# 03-PeripheralPart-V2_4.net
KiCad netlist of a schematic drawn in Altium Designer
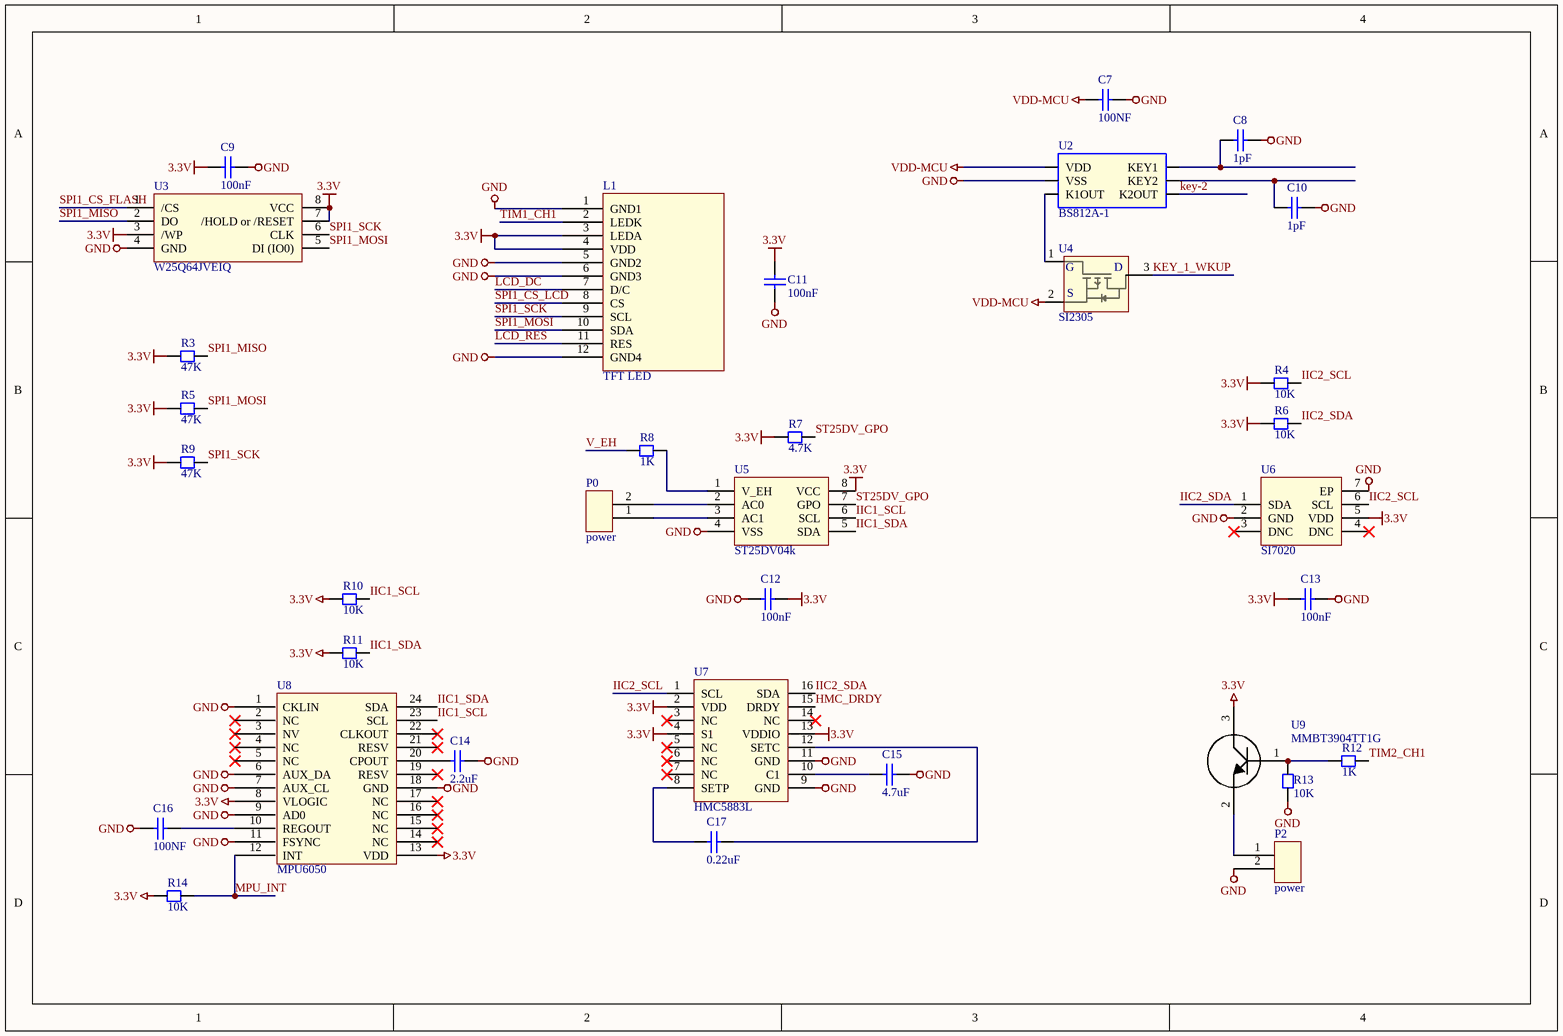
[diagram p0: 03-PeripheralPart-V2.4.SchDoc]

(export (version "E")
  (design (tool "Eeschema 10.0.6"))
  (components
    (comp (ref "C7")
      (value "100NF")
      (footprint "CC1005-0402")
      (description "贴片电容")
      (libsource (lib "tianxiaohua_Schlib") (part "Chip capacitor"))
    )
    (comp (ref "C8")
      (value "1pF")
      (footprint "CC1005-0402")
      (description "贴片电容")
      (libsource (lib "tianxiaohua_Schlib") (part "Chip capacitor"))
    )
    (comp (ref "C9")
      (value "100nF")
      (footprint "CC1005-0402")
      (description "贴片电容")
      (libsource (lib "tianxiaohua_Schlib") (part "Chip capacitor"))
    )
    (comp (ref "C10")
      (value "1pF")
      (footprint "CC1005-0402")
      (description "贴片电容")
      (libsource (lib "tianxiaohua_Schlib") (part "Chip capacitor"))
    )
    (comp (ref "C11")
      (value "100nF")
      (footprint "CC1005-0402")
      (description "贴片电容")
      (libsource (lib "tianxiaohua_Schlib") (part "Chip capacitor"))
    )
    (comp (ref "C12")
      (value "100nF")
      (footprint "CC1005-0402")
      (description "贴片电容")
      (libsource (lib "tianxiaohua_Schlib") (part "Chip capacitor"))
    )
    (comp (ref "C13")
      (value "100nF")
      (footprint "CC1005-0402")
      (description "贴片电容")
      (libsource (lib "tianxiaohua_Schlib") (part "Chip capacitor"))
    )
    (comp (ref "C14")
      (value "2.2uF")
      (footprint "CC1005-0402")
      (description "贴片电容")
      (libsource (lib "tianxiaohua_Schlib") (part "Chip capacitor"))
    )
    (comp (ref "C15")
      (value "4.7uF")
      (footprint "CC1005-0402")
      (description "贴片电容")
      (libsource (lib "tianxiaohua_Schlib") (part "Chip capacitor"))
    )
    (comp (ref "C16")
      (value "100NF")
      (footprint "CC1005-0402")
      (description "贴片电容")
      (libsource (lib "tianxiaohua_Schlib") (part "Chip capacitor"))
    )
    (comp (ref "C17")
      (value "0.22uF")
      (footprint "CC1005-0402")
      (description "贴片电容")
      (libsource (lib "tianxiaohua_Schlib") (part "Chip capacitor"))
    )
    (comp (ref "L1")
      (value "TFT LED")
      (footprint "LCD-1.3-(2)")
      (description "1.3寸显示屏幕")
      (libsource (lib "tianxiaohua_Schlib") (part "LCD-IPSscreen-1.3"))
    )
    (comp (ref "P0") (value "power") (footprint "POWER2") (libsource (lib "") (part "power_1")))
    (comp (ref "P2")
      (value "power")
      (footprint "POWER-3.7V")
      (libsource (lib "tianxiaohua_Schlib") (part "power"))
    )
    (comp (ref "R3")
      (value "47K")
      (footprint "CR1005-0402")
      (description "贴片电阻")
      (libsource (lib "") (part "Chip resistor_1"))
    )
    (comp (ref "R4")
      (value "10K")
      (footprint "CR1005-0402")
      (description "贴片电阻")
      (libsource (lib "") (part "Chip resistor_1"))
    )
    (comp (ref "R5")
      (value "47K")
      (footprint "CR1005-0402")
      (description "贴片电阻")
      (libsource (lib "") (part "Chip resistor_1"))
    )
    (comp (ref "R6")
      (value "10K")
      (footprint "CR1005-0402")
      (description "贴片电阻")
      (libsource (lib "") (part "Chip resistor_1"))
    )
    (comp (ref "R7")
      (value "4.7K")
      (footprint "CR1005-0402")
      (description "贴片电阻")
      (libsource (lib "") (part "Chip resistor_2"))
    )
    (comp (ref "R8")
      (value "1K")
      (footprint "CR1005-0402")
      (description "贴片电阻")
      (libsource (lib "") (part "Chip resistor_1"))
    )
    (comp (ref "R9")
      (value "47K")
      (footprint "CR1005-0402")
      (description "贴片电阻")
      (libsource (lib "") (part "Chip resistor_1"))
    )
    (comp (ref "R10")
      (value "10K")
      (footprint "CR1005-0402")
      (description "贴片电阻")
      (libsource (lib "") (part "Chip resistor_1"))
    )
    (comp (ref "R11")
      (value "10K")
      (footprint "CR1005-0402")
      (description "贴片电阻")
      (libsource (lib "") (part "Chip resistor_1"))
    )
    (comp (ref "R12")
      (value "1K")
      (footprint "CR1005-0402")
      (description "贴片电阻")
      (libsource (lib "") (part "Chip resistor_1"))
    )
    (comp (ref "R13")
      (value "10K")
      (footprint "CR1005-0402")
      (description "贴片电阻")
      (libsource (lib "tianxiaohua_Schlib") (part "Chip resistor"))
    )
    (comp (ref "R14")
      (value "10K")
      (footprint "CR1005-0402")
      (description "贴片电阻")
      (libsource (lib "") (part "Chip resistor_1"))
    )
    (comp (ref "U2")
      (value "BS812A-1")
      (footprint "SOT23-6")
      (description "触摸按键 两路 SOP23-6封装极简电路")
      (libsource (lib "tianxiaohua_Schlib") (part "BS812A-1"))
    )
    (comp (ref "U3")
      (value "W25Q64JVEIQ")
      (footprint "WSON-8_L8.0-W6.10-P1.27-TL-EP")
      (description "FLASH")
      (libsource (lib "tianxiaohua_Schlib") (part "W25Q256JVEIQ"))
    )
    (comp (ref "U4")
      (value "SI2305")
      (footprint "SOT-23")
      (description "PMOS场效应MOS管 SOT-23")
      (libsource (lib "tianxiaohua_Schlib") (part "SI2305"))
    )
    (comp (ref "U5")
      (value "ST25DV04k")
      (footprint "UFDFPN8")
      (description "NFC芯片4K存储空间")
      (libsource (lib "tianxiaohua_Schlib") (part "ST25DV04k"))
    )
    (comp (ref "U6")
      (value "SI7020")
      (footprint "DFN-6")
      (description "温湿度传感器芯片")
      (libsource (lib "tianxiaohua_Schlib") (part "SI7020"))
    )
    (comp (ref "U7")
      (value "HMC5883L")
      (footprint "LPCC-16_L3.0-W3.0-P0.50-BL")
      (description "三轴罗盘")
      (libsource (lib "tianxiaohua_Schlib") (part "HMC5883L"))
    )
    (comp (ref "U8")
      (value "MPU6050")
      (footprint "QFN24 - duplicate")
      (description "陀螺仪")
      (libsource (lib "tianxiaohua_Schlib") (part "MPU6050"))
    )
    (comp (ref "U9")
      (value "MMBT3904TT1G")
      (footprint "SOT-416")
      (description "NPN 电流 - 集电极（Ic）（最大值）：200mA 电压 - 集射极击穿（最大值）：40V SOT-23-3")
      (libsource (lib "tianxiaohua_Schlib") (part "MMBT3904TT1G"))
    )
  )
  (nets
    (net (code "1") (name "/HMC_DRDY") (class "Default")
      (node (ref "U7") (pin "15") (pinfunction "DRDY_15") (pintype "passive"))
    )
    (net (code "2") (name "/IIC1_SCL") (class "Default")
      (node (ref "R10") (pin "1") (pinfunction "1_1") (pintype "passive"))
      (node (ref "U5") (pin "6") (pinfunction "SCL_6") (pintype "passive"))
      (node (ref "U8") (pin "23") (pinfunction "SCL_23") (pintype "passive"))
    )
    (net (code "3") (name "/IIC1_SDA") (class "Default")
      (node (ref "R11") (pin "1") (pinfunction "1_1") (pintype "passive"))
      (node (ref "U5") (pin "5") (pinfunction "SDA_5") (pintype "passive"))
      (node (ref "U8") (pin "24") (pinfunction "SDA_24") (pintype "passive"))
    )
    (net (code "4") (name "/IIC2_SCL") (class "Default")
      (node (ref "R4") (pin "1") (pinfunction "1_1") (pintype "passive"))
      (node (ref "U6") (pin "6") (pinfunction "SCL_6") (pintype "passive"))
      (node (ref "U7") (pin "1") (pinfunction "SCL_1") (pintype "passive"))
    )
    (net (code "5") (name "/IIC2_SDA") (class "Default")
      (node (ref "R6") (pin "1") (pinfunction "1_1") (pintype "passive"))
      (node (ref "U6") (pin "1") (pinfunction "SDA_1") (pintype "passive"))
      (node (ref "U7") (pin "16") (pinfunction "SDA_16") (pintype "passive"))
    )
    (net (code "6") (name "/KEY_1_WKUP") (class "Default")
      (node (ref "U4") (pin "3") (pinfunction "DRAIN_3") (pintype "passive"))
    )
    (net (code "7") (name "/LCD_DC") (class "Default")
      (node (ref "L1") (pin "7") (pinfunction "D/C_7") (pintype "passive"))
    )
    (net (code "8") (name "/LCD_RES") (class "Default")
      (node (ref "L1") (pin "11") (pinfunction "RES_11") (pintype "passive"))
    )
    (net (code "9") (name "/MPU_INT") (class "Default")
      (node (ref "R14") (pin "1") (pinfunction "1_1") (pintype "passive"))
      (node (ref "U8") (pin "12") (pinfunction "INT_12") (pintype "passive"))
    )
    (net (code "10") (name "/SPI1_CS_FLASH") (class "Default")
      (node (ref "U3") (pin "1") (pinfunction "/CS_1") (pintype "passive"))
    )
    (net (code "11") (name "/SPI1_CS_LCD") (class "Default")
      (node (ref "L1") (pin "8") (pinfunction "CS_8") (pintype "passive"))
    )
    (net (code "12") (name "/SPI1_MISO") (class "Default")
      (node (ref "R3") (pin "1") (pinfunction "1_1") (pintype "passive"))
      (node (ref "U3") (pin "2") (pinfunction "DO_2") (pintype "passive"))
    )
    (net (code "13") (name "/SPI1_MOSI") (class "Default")
      (node (ref "L1") (pin "10") (pinfunction "SDA_10") (pintype "passive"))
      (node (ref "R5") (pin "1") (pinfunction "1_1") (pintype "passive"))
      (node (ref "U3") (pin "5") (pinfunction "DI_(IO0)_5") (pintype "passive"))
    )
    (net (code "14") (name "/SPI1_SCK") (class "Default")
      (node (ref "L1") (pin "9") (pinfunction "SCL_9") (pintype "passive"))
      (node (ref "R9") (pin "1") (pinfunction "1_1") (pintype "passive"))
      (node (ref "U3") (pin "6") (pinfunction "CLK_6") (pintype "passive"))
    )
    (net (code "15") (name "/ST25DV_GPO") (class "Default")
      (node (ref "R7") (pin "2") (pinfunction "2_2") (pintype "passive"))
      (node (ref "U5") (pin "7") (pinfunction "GPO_7") (pintype "passive"))
    )
    (net (code "16") (name "/TIM1_CH1") (class "Default")
      (node (ref "L1") (pin "2") (pinfunction "LEDK_2") (pintype "passive"))
    )
    (net (code "17") (name "/TIM2_CH1") (class "Default")
      (node (ref "R12") (pin "1") (pinfunction "1_1") (pintype "passive"))
    )
    (net (code "18") (name "/V_EH") (class "Default")
      (node (ref "R8") (pin "2") (pinfunction "2_2") (pintype "passive"))
    )
    (net (code "19") (name "/key-2") (class "Default")
      (node (ref "U2") (pin "4") (pinfunction "K2OUT_4") (pintype "passive"))
    )
    (net (code "20") (name "3.3V") (class "Default")
      (node (ref "C11") (pin "1") (pinfunction "1_1") (pintype "passive"))
      (node (ref "C12") (pin "2") (pinfunction "2_2") (pintype "passive"))
      (node (ref "C13") (pin "1") (pinfunction "1_1") (pintype "passive"))
      (node (ref "C9") (pin "1") (pinfunction "1_1") (pintype "passive"))
      (node (ref "L1") (pin "3") (pinfunction "LEDA_3") (pintype "passive"))
      (node (ref "L1") (pin "4") (pinfunction "VDD_4") (pintype "passive"))
      (node (ref "R10") (pin "2") (pinfunction "2_2") (pintype "passive"))
      (node (ref "R11") (pin "2") (pinfunction "2_2") (pintype "passive"))
      (node (ref "R14") (pin "2") (pinfunction "2_2") (pintype "passive"))
      (node (ref "R3") (pin "2") (pinfunction "2_2") (pintype "passive"))
      (node (ref "R4") (pin "2") (pinfunction "2_2") (pintype "passive"))
      (node (ref "R5") (pin "2") (pinfunction "2_2") (pintype "passive"))
      (node (ref "R6") (pin "2") (pinfunction "2_2") (pintype "passive"))
      (node (ref "R7") (pin "1") (pinfunction "1_1") (pintype "passive"))
      (node (ref "R9") (pin "2") (pinfunction "2_2") (pintype "passive"))
      (node (ref "U3") (pin "3") (pinfunction "/WP_3") (pintype "passive"))
      (node (ref "U3") (pin "7") (pinfunction "/HOLD_or_/RESET_7") (pintype "passive"))
      (node (ref "U3") (pin "8") (pinfunction "VCC_8") (pintype "passive"))
      (node (ref "U5") (pin "8") (pinfunction "VCC_8") (pintype "passive"))
      (node (ref "U6") (pin "5") (pinfunction "VDD_5") (pintype "passive"))
      (node (ref "U7") (pin "13") (pinfunction "VDDIO_13") (pintype "passive"))
      (node (ref "U7") (pin "2") (pinfunction "VDD_2") (pintype "passive"))
      (node (ref "U7") (pin "4") (pinfunction "S1_4") (pintype "passive"))
      (node (ref "U8") (pin "13") (pinfunction "VDD_13") (pintype "passive"))
      (node (ref "U8") (pin "8") (pinfunction "VLOGIC_8") (pintype "passive"))
      (node (ref "U9") (pin "3") (pinfunction "3_3") (pintype "passive"))
    )
    (net (code "21") (name "GND") (class "Default")
      (node (ref "C10") (pin "2") (pinfunction "2_2") (pintype "passive"))
      (node (ref "C11") (pin "2") (pinfunction "2_2") (pintype "passive"))
      (node (ref "C12") (pin "1") (pinfunction "1_1") (pintype "passive"))
      (node (ref "C13") (pin "2") (pinfunction "2_2") (pintype "passive"))
      (node (ref "C14") (pin "2") (pinfunction "2_2") (pintype "passive"))
      (node (ref "C15") (pin "2") (pinfunction "2_2") (pintype "passive"))
      (node (ref "C16") (pin "1") (pinfunction "1_1") (pintype "passive"))
      (node (ref "C7") (pin "1") (pinfunction "1_1") (pintype "passive"))
      (node (ref "C8") (pin "2") (pinfunction "2_2") (pintype "passive"))
      (node (ref "C9") (pin "2") (pinfunction "2_2") (pintype "passive"))
      (node (ref "L1") (pin "1") (pinfunction "GND1_1") (pintype "passive"))
      (node (ref "L1") (pin "12") (pinfunction "GND4_12") (pintype "passive"))
      (node (ref "L1") (pin "5") (pinfunction "GND2_5") (pintype "passive"))
      (node (ref "L1") (pin "6") (pinfunction "GND3_6") (pintype "passive"))
      (node (ref "P2") (pin "2") (pinfunction "2_2") (pintype "passive"))
      (node (ref "R13") (pin "2") (pinfunction "2_2") (pintype "passive"))
      (node (ref "U2") (pin "2") (pinfunction "VSS_2") (pintype "passive"))
      (node (ref "U3") (pin "4") (pinfunction "GND_4") (pintype "passive"))
      (node (ref "U5") (pin "4") (pinfunction "VSS_4") (pintype "passive"))
      (node (ref "U6") (pin "2") (pinfunction "GND_2") (pintype "passive"))
      (node (ref "U6") (pin "7") (pinfunction "EP_7") (pintype "passive"))
      (node (ref "U7") (pin "11") (pinfunction "GND_11") (pintype "passive"))
      (node (ref "U7") (pin "9") (pinfunction "GND_9") (pintype "passive"))
      (node (ref "U8") (pin "1") (pinfunction "CKLIN_1") (pintype "passive"))
      (node (ref "U8") (pin "11") (pinfunction "FSYNC_11") (pintype "passive"))
      (node (ref "U8") (pin "18") (pinfunction "GND_18") (pintype "passive"))
      (node (ref "U8") (pin "6") (pinfunction "AUX_DA_6") (pintype "passive"))
      (node (ref "U8") (pin "7") (pinfunction "AUX_CL_7") (pintype "passive"))
      (node (ref "U8") (pin "9") (pinfunction "AD0_9") (pintype "passive"))
    )
    (net (code "22") (name "Net-(P2-Pad1)") (class "Default")
      (node (ref "P2") (pin "1") (pinfunction "1_1") (pintype "passive"))
      (node (ref "U9") (pin "2") (pinfunction "2_2") (pintype "passive"))
    )
    (net (code "23") (name "Net-(R12-Pad2)") (class "Default")
      (node (ref "R12") (pin "2") (pinfunction "2_2") (pintype "passive"))
      (node (ref "R13") (pin "1") (pinfunction "1_1") (pintype "passive"))
      (node (ref "U9") (pin "1") (pinfunction "1_1") (pintype "passive"))
    )
    (net (code "24") (name "Net-(U2-K1OUT)") (class "Default")
      (node (ref "U2") (pin "3") (pinfunction "K1OUT_3") (pintype "passive"))
      (node (ref "U4") (pin "1") (pinfunction "GATE_1") (pintype "passive"))
    )
    (net (code "25") (name "Net-(U2-KEY1)") (class "Default")
      (node (ref "C8") (pin "1") (pinfunction "1_1") (pintype "passive"))
      (node (ref "U2") (pin "6") (pinfunction "KEY1_6") (pintype "passive"))
    )
    (net (code "26") (name "Net-(U2-KEY2)") (class "Default")
      (node (ref "C10") (pin "1") (pinfunction "1_1") (pintype "passive"))
      (node (ref "U2") (pin "5") (pinfunction "KEY2_5") (pintype "passive"))
    )
    (net (code "27") (name "Net-(U5-AC0)") (class "Default")
      (node (ref "P0") (pin "2") (pinfunction "2_2") (pintype "passive"))
      (node (ref "U5") (pin "2") (pinfunction "AC0_2") (pintype "passive"))
    )
    (net (code "28") (name "Net-(U5-AC1)") (class "Default")
      (node (ref "P0") (pin "1") (pinfunction "1_1") (pintype "passive"))
      (node (ref "U5") (pin "3") (pinfunction "AC1_3") (pintype "passive"))
    )
    (net (code "29") (name "Net-(U5-V_EH)") (class "Default")
      (node (ref "R8") (pin "1") (pinfunction "1_1") (pintype "passive"))
      (node (ref "U5") (pin "1") (pinfunction "V_EH_1") (pintype "passive"))
    )
    (net (code "30") (name "Net-(U7-C1)") (class "Default")
      (node (ref "C15") (pin "1") (pinfunction "1_1") (pintype "passive"))
      (node (ref "U7") (pin "10") (pinfunction "C1_10") (pintype "passive"))
    )
    (net (code "31") (name "Net-(U7-SETC)") (class "Default")
      (node (ref "C17") (pin "2") (pinfunction "2_2") (pintype "passive"))
      (node (ref "U7") (pin "12") (pinfunction "SETC_12") (pintype "passive"))
    )
    (net (code "32") (name "Net-(U7-SETP)") (class "Default")
      (node (ref "C17") (pin "1") (pinfunction "1_1") (pintype "passive"))
      (node (ref "U7") (pin "8") (pinfunction "SETP_8") (pintype "passive"))
    )
    (net (code "33") (name "Net-(U8-CPOUT)") (class "Default")
      (node (ref "C14") (pin "1") (pinfunction "1_1") (pintype "passive"))
      (node (ref "U8") (pin "20") (pinfunction "CPOUT_20") (pintype "passive"))
    )
    (net (code "34") (name "Net-(U8-REGOUT)") (class "Default")
      (node (ref "C16") (pin "2") (pinfunction "2_2") (pintype "passive"))
      (node (ref "U8") (pin "10") (pinfunction "REGOUT_10") (pintype "passive"))
    )
    (net (code "35") (name "VDD-MCU") (class "Default")
      (node (ref "C7") (pin "2") (pinfunction "2_2") (pintype "passive"))
      (node (ref "U2") (pin "1") (pinfunction "VDD_1") (pintype "passive"))
      (node (ref "U4") (pin "2") (pinfunction "SOURCE_2") (pintype "passive"))
    )
    (net (code "36") (name "unconnected-(U6-DNC-Pad3)") (class "Default")
      (node (ref "U6") (pin "3") (pinfunction "DNC_3") (pintype "passive+no_connect"))
    )
    (net (code "37") (name "unconnected-(U6-DNC-Pad4)") (class "Default")
      (node (ref "U6") (pin "4") (pinfunction "DNC_4") (pintype "passive+no_connect"))
    )
    (net (code "38") (name "unconnected-(U7-NC-Pad3)") (class "Default")
      (node (ref "U7") (pin "3") (pinfunction "NC_3") (pintype "passive+no_connect"))
    )
    (net (code "39") (name "unconnected-(U7-NC-Pad5)") (class "Default")
      (node (ref "U7") (pin "5") (pinfunction "NC_5") (pintype "passive+no_connect"))
    )
    (net (code "40") (name "unconnected-(U7-NC-Pad6)") (class "Default")
      (node (ref "U7") (pin "6") (pinfunction "NC_6") (pintype "passive+no_connect"))
    )
    (net (code "41") (name "unconnected-(U7-NC-Pad7)") (class "Default")
      (node (ref "U7") (pin "7") (pinfunction "NC_7") (pintype "passive+no_connect"))
    )
    (net (code "42") (name "unconnected-(U7-NC-Pad14)") (class "Default")
      (node (ref "U7") (pin "14") (pinfunction "NC_14") (pintype "passive+no_connect"))
    )
    (net (code "43") (name "unconnected-(U8-CLKOUT-Pad22)") (class "Default")
      (node (ref "U8") (pin "22") (pinfunction "CLKOUT_22") (pintype "passive+no_connect"))
    )
    (net (code "44") (name "unconnected-(U8-NC-Pad2)") (class "Default")
      (node (ref "U8") (pin "2") (pinfunction "NC_2") (pintype "passive+no_connect"))
    )
    (net (code "45") (name "unconnected-(U8-NC-Pad4)") (class "Default")
      (node (ref "U8") (pin "4") (pinfunction "NC_4") (pintype "passive+no_connect"))
    )
    (net (code "46") (name "unconnected-(U8-NC-Pad5)") (class "Default")
      (node (ref "U8") (pin "5") (pinfunction "NC_5") (pintype "passive+no_connect"))
    )
    (net (code "47") (name "unconnected-(U8-NC-Pad14)") (class "Default")
      (node (ref "U8") (pin "14") (pinfunction "NC_14") (pintype "passive+no_connect"))
    )
    (net (code "48") (name "unconnected-(U8-NC-Pad15)") (class "Default")
      (node (ref "U8") (pin "15") (pinfunction "NC_15") (pintype "passive+no_connect"))
    )
    (net (code "49") (name "unconnected-(U8-NC-Pad16)") (class "Default")
      (node (ref "U8") (pin "16") (pinfunction "NC_16") (pintype "passive+no_connect"))
    )
    (net (code "50") (name "unconnected-(U8-NC-Pad17)") (class "Default")
      (node (ref "U8") (pin "17") (pinfunction "NC_17") (pintype "passive+no_connect"))
    )
    (net (code "51") (name "unconnected-(U8-NV-Pad3)") (class "Default")
      (node (ref "U8") (pin "3") (pinfunction "NV_3") (pintype "passive+no_connect"))
    )
    (net (code "52") (name "unconnected-(U8-RESV-Pad19)") (class "Default")
      (node (ref "U8") (pin "19") (pinfunction "RESV_19") (pintype "passive+no_connect"))
    )
    (net (code "53") (name "unconnected-(U8-RESV-Pad21)") (class "Default")
      (node (ref "U8") (pin "21") (pinfunction "RESV_21") (pintype "passive+no_connect"))
    )
  )
)
